# Sensors.net
KiCad netlist of a schematic drawn in Altium Designer
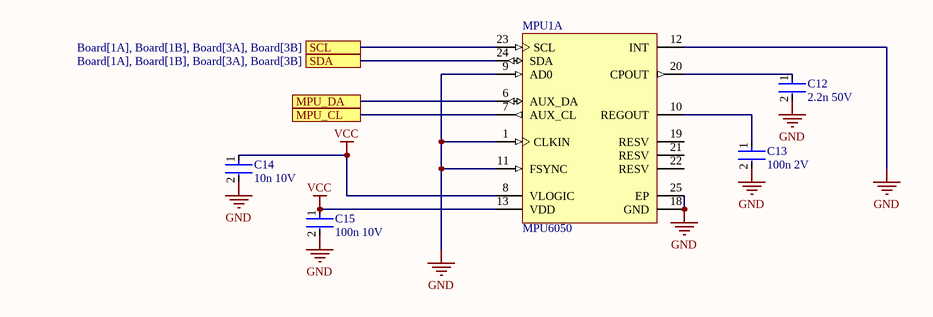
[diagram p0: Sensors.SchDoc]

(export (version "E")
  (design (tool "Eeschema 10.0.6"))
  (components
    (comp (ref "C12")
      (value "2.2n 50V")
      (footprint "FP-GRM155-0_05-MFG")
      (description "Chip Multilayer Ceramic Capacitors for General Purpose, 0402, 390pF, C0G, 30ppm/°C, 5%, 50V")
      (fields (field (name "TOLERANCE") "5%") (field (name "VOLTAGE") "50V"))
      (libsource (lib "Altium Content Vault") (part "02cd4be3c70576c341d710602a673aa"))
    )
    (comp (ref "C13")
      (value "100n 2V")
      (footprint "FP-GRM155-0_05-MFG")
      (description "Chip Multilayer Ceramic Capacitors for General Purpose, 0402, 390pF, C0G, 30ppm/°C, 5%, 50V")
      (fields (field (name "TOLERANCE") "5%") (field (name "VOLTAGE") "50V"))
      (libsource (lib "Altium Content Vault") (part "02cd4be3c70576c341d710602a673aa"))
    )
    (comp (ref "C14")
      (value "10n 10V")
      (footprint "FP-GRM155-0_05-MFG")
      (description "Chip Multilayer Ceramic Capacitors for General Purpose, 0402, 390pF, C0G, 30ppm/°C, 5%, 50V")
      (fields (field (name "TOLERANCE") "5%") (field (name "VOLTAGE") "50V"))
      (libsource (lib "Altium Content Vault") (part "02cd4be3c70576c341d710602a673aa"))
    )
    (comp (ref "C15")
      (value "100n 10V")
      (footprint "FP-GRM155-0_05-MFG")
      (description "Chip Multilayer Ceramic Capacitors for General Purpose, 0402, 390pF, C0G, 30ppm/°C, 5%, 50V")
      (fields (field (name "TOLERANCE") "5%") (field (name "VOLTAGE") "50V"))
      (libsource (lib "Altium Content Vault") (part "02cd4be3c70576c341d710602a673aa"))
    )
    (comp (ref "MPU1")
      (value "MPU6050")
      (footprint "INSE-QFN-24_V")
      (fields (field (name "MANUFACTURER") "InvenSense"))
      (libsource (lib "Politechnika Wrocławska") (part "INSE-MPU6050-QFN-24"))
    )
  )
  (nets
    (net (code "1") (name "/MPU_CL") (class "Default")
      (node (ref "MPU1") (pin "7") (pinfunction "AUX_CL_7") (pintype "output"))
    )
    (net (code "2") (name "/MPU_DA") (class "Default")
      (node (ref "MPU1") (pin "6") (pinfunction "AUX_DA_6") (pintype "bidirectional"))
    )
    (net (code "3") (name "/SCL") (class "Default")
      (node (ref "MPU1") (pin "23") (pinfunction "SCL_23") (pintype "input"))
    )
    (net (code "4") (name "/SDA") (class "Default")
      (node (ref "MPU1") (pin "24") (pinfunction "SDA_24") (pintype "bidirectional"))
    )
    (net (code "5") (name "GND") (class "Default")
      (node (ref "C12") (pin "2") (pinfunction "2_2") (pintype "passive"))
      (node (ref "C13") (pin "2") (pinfunction "2_2") (pintype "passive"))
      (node (ref "C14") (pin "2") (pinfunction "2_2") (pintype "passive"))
      (node (ref "C15") (pin "2") (pinfunction "2_2") (pintype "passive"))
      (node (ref "MPU1") (pin "1") (pinfunction "CLKIN_1") (pintype "input"))
      (node (ref "MPU1") (pin "11") (pinfunction "FSYNC_11") (pintype "input"))
      (node (ref "MPU1") (pin "12") (pinfunction "INT_12") (pintype "open_collector"))
      (node (ref "MPU1") (pin "18") (pinfunction "GND_18") (pintype "power_in"))
      (node (ref "MPU1") (pin "25") (pinfunction "EP_25") (pintype "passive"))
      (node (ref "MPU1") (pin "9") (pinfunction "AD0_9") (pintype "input"))
    )
    (net (code "6") (name "Net-(MPU1A-CPOUT)") (class "Default")
      (node (ref "C12") (pin "1") (pinfunction "1_1") (pintype "passive"))
      (node (ref "MPU1") (pin "20") (pinfunction "CPOUT_20") (pintype "output"))
    )
    (net (code "7") (name "Net-(MPU1A-REGOUT)") (class "Default")
      (node (ref "C13") (pin "1") (pinfunction "1_1") (pintype "passive"))
      (node (ref "MPU1") (pin "10") (pinfunction "REGOUT_10") (pintype "passive"))
    )
    (net (code "8") (name "VCC") (class "Default")
      (node (ref "C14") (pin "1") (pinfunction "1_1") (pintype "passive"))
      (node (ref "C15") (pin "1") (pinfunction "1_1") (pintype "passive"))
      (node (ref "MPU1") (pin "13") (pinfunction "VDD_13") (pintype "power_in"))
      (node (ref "MPU1") (pin "8") (pinfunction "VLOGIC_8") (pintype "power_in"))
    )
    (net (code "9") (name "unconnected-(MPU1A-RESV-Pad19)") (class "Default")
      (node (ref "MPU1") (pin "19") (pinfunction "RESV_19") (pintype "passive"))
    )
    (net (code "10") (name "unconnected-(MPU1A-RESV-Pad21)") (class "Default")
      (node (ref "MPU1") (pin "21") (pinfunction "RESV_21") (pintype "passive"))
    )
    (net (code "11") (name "unconnected-(MPU1A-RESV-Pad22)") (class "Default")
      (node (ref "MPU1") (pin "22") (pinfunction "RESV_22") (pintype "passive"))
    )
  )
)
